# 20190906TPS40200CV.net
KiCad netlist of a schematic drawn in Altium Designer
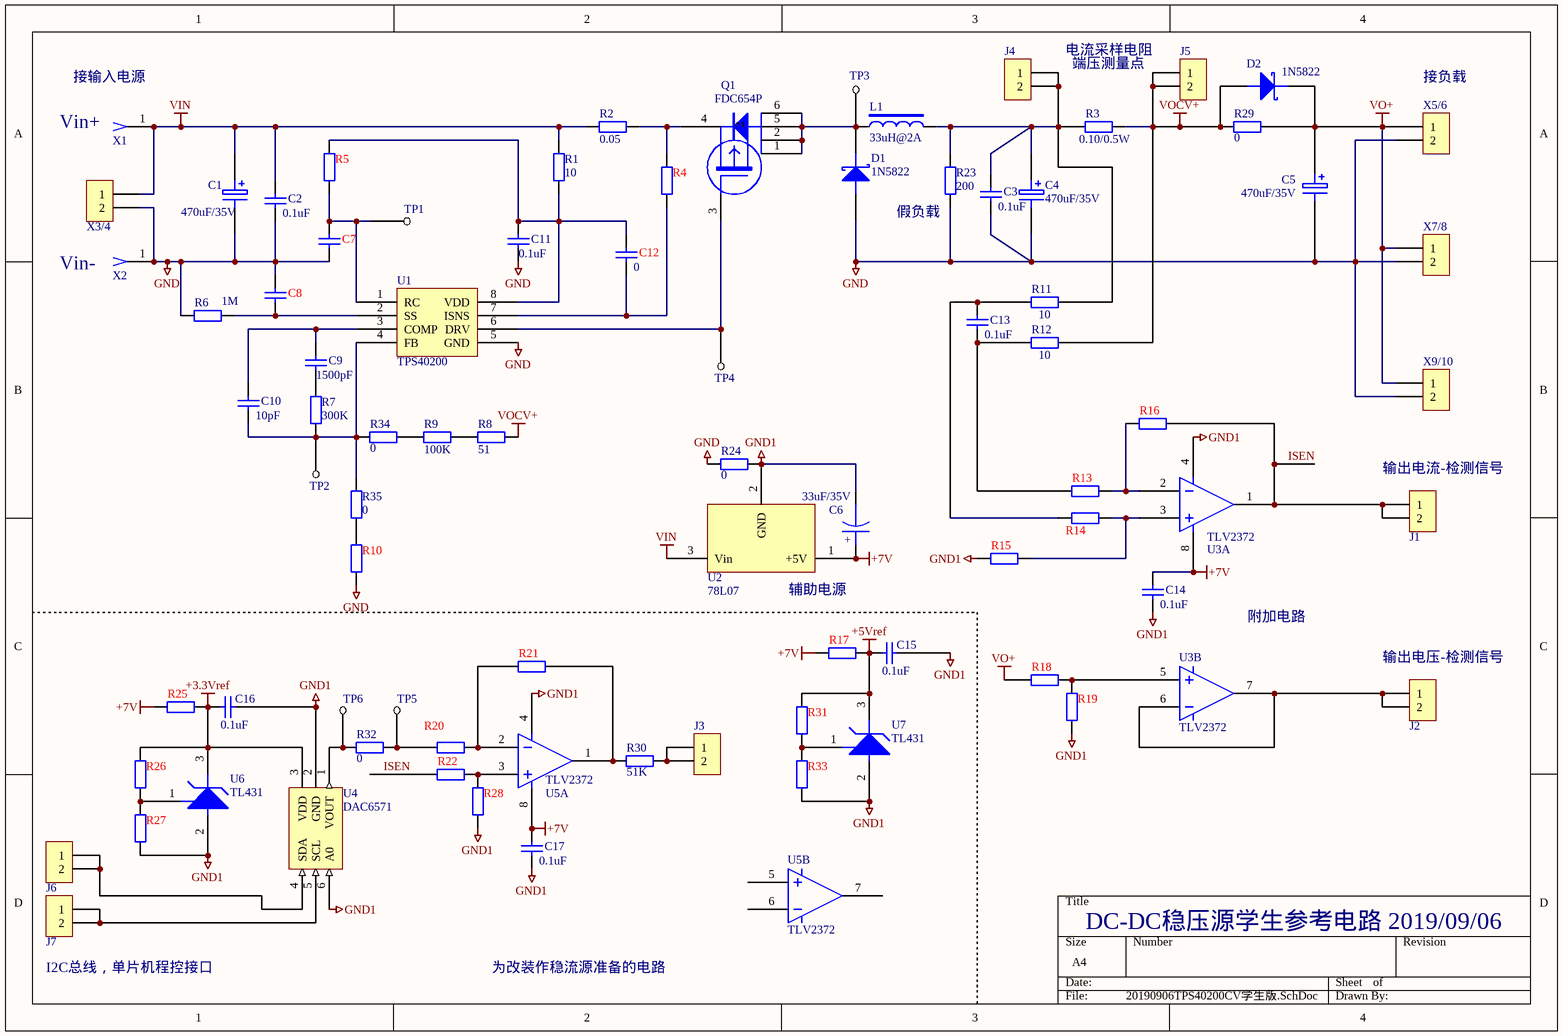
[diagram p0: 20190906TPS40200CV学生版.SchDoc]

(export (version "E")
  (design (tool "Eeschema 10.0.6"))
  (components
    (comp (ref "C1")
      (value "470uF/35V")
      (footprint "RB5-10.5")
      (description "Electrolytic Capacitor")
      (libsource (lib "*") (part "ELECTRO1"))
    )
    (comp (ref "C2")
      (value "0.1uF")
      (footprint "0805-1")
      (description "Capacitor")
      (fields (field (name "PUBLISHER") "Altium Limited"))
      (libsource (lib "Miscellaneous Devices") (part "Cap"))
    )
    (comp (ref "C3")
      (value "0.1uF")
      (footprint "0805-1")
      (description "Capacitor")
      (fields (field (name "PUBLISHER") "Altium Limited"))
      (libsource (lib "Miscellaneous Devices") (part "Cap"))
    )
    (comp (ref "C4")
      (value "470uF/35V")
      (footprint "RB5-10.5")
      (description "Electrolytic Capacitor")
      (libsource (lib "*") (part "ELECTRO1"))
    )
    (comp (ref "C5")
      (value "470uF/35V")
      (footprint "RB5-10.5")
      (description "Electrolytic Capacitor")
      (libsource (lib "*") (part "ELECTRO1"))
    )
    (comp (ref "C6")
      (value "33uF/35V")
      (footprint "C-RB-8")
      (description "Capacitor")
      (libsource (lib "*") (part "CAPACITOR POL"))
    )
    (comp (ref "C7")
      (value "~")
      (footprint "0805-1")
      (description "Capacitor")
      (fields (field (name "PUBLISHER") "Altium Limited"))
      (libsource (lib "Miscellaneous Devices") (part "Cap"))
    )
    (comp (ref "C8")
      (value "~")
      (footprint "0805-1")
      (description "Capacitor")
      (fields (field (name "PUBLISHER") "Altium Limited"))
      (libsource (lib "Miscellaneous Devices") (part "Cap"))
    )
    (comp (ref "C9")
      (value "1500pF")
      (footprint "0805-1")
      (description "Capacitor")
      (fields (field (name "PUBLISHER") "Altium Limited"))
      (libsource (lib "Miscellaneous Devices") (part "Cap"))
    )
    (comp (ref "C10")
      (value "10pF")
      (footprint "0805-1")
      (description "Capacitor")
      (fields (field (name "PUBLISHER") "Altium Limited"))
      (libsource (lib "Miscellaneous Devices") (part "Cap"))
    )
    (comp (ref "C11")
      (value "0.1uF")
      (footprint "0805-1")
      (description "Capacitor")
      (fields (field (name "PUBLISHER") "Altium Limited"))
      (libsource (lib "Miscellaneous Devices") (part "Cap"))
    )
    (comp (ref "C12")
      (value "0")
      (footprint "0805-1")
      (description "Capacitor")
      (fields (field (name "PUBLISHER") "Altium Limited"))
      (libsource (lib "Miscellaneous Devices") (part "Cap"))
    )
    (comp (ref "C13")
      (value "0.1uF")
      (footprint "0805-1")
      (description "Capacitor")
      (fields (field (name "PUBLISHER") "Altium Limited"))
      (libsource (lib "Miscellaneous Devices") (part "Cap"))
    )
    (comp (ref "C14")
      (value "0.1uF")
      (footprint "0805-1")
      (description "Capacitor")
      (fields (field (name "PUBLISHER") "Altium Limited"))
      (libsource (lib "Miscellaneous Devices") (part "Cap"))
    )
    (comp (ref "C15")
      (value "0.1uF")
      (footprint "CC2012-0805")
      (description "Capacitor")
      (fields (field (name "PUBLISHER") "Altium Limited"))
      (libsource (lib "Miscellaneous Devices") (part "Cap"))
    )
    (comp (ref "C16")
      (value "0.1uF")
      (footprint "0805-1")
      (description "Capacitor")
      (fields (field (name "PUBLISHER") "Altium Limited"))
      (libsource (lib "Miscellaneous Devices") (part "Cap"))
    )
    (comp (ref "C17")
      (value "0.1uF")
      (footprint "0805-1")
      (description "Capacitor")
      (fields (field (name "PUBLISHER") "Altium Limited"))
      (libsource (lib "Miscellaneous Devices") (part "Cap"))
    )
    (comp (ref "D1")
      (value "1N5822")
      (footprint "DIODE-0.7")
      (description "Schottky Diode")
      (libsource (lib "*") (part "DIODE SCHOTTKY"))
    )
    (comp (ref "D2")
      (value "1N5822")
      (footprint "DIODE-0.7")
      (description "Schottky Diode")
      (libsource (lib "*") (part "DIODE SCHOTTKY"))
    )
    (comp (ref "J1")
      (value "SIP2")
      (footprint "HDR1X2")
      (description "Connector")
      (libsource (lib "*") (part "CON2"))
    )
    (comp (ref "J2")
      (value "SIP2")
      (footprint "HDR1X2")
      (description "Connector")
      (libsource (lib "*") (part "CON2"))
    )
    (comp (ref "J3")
      (value "SIP2")
      (footprint "HDR1X2")
      (description "Connector")
      (libsource (lib "*") (part "CON2"))
    )
    (comp (ref "J4")
      (value "SIP2")
      (footprint "HDR1X2")
      (description "Connector")
      (libsource (lib "") (part "CON2_1"))
    )
    (comp (ref "J5")
      (value "SIP2")
      (footprint "HDR1X2")
      (description "Connector")
      (libsource (lib "*") (part "CON2"))
    )
    (comp (ref "J6")
      (value "SIP2")
      (footprint "HDR1X2")
      (description "Connector")
      (libsource (lib "") (part "CON2_1"))
    )
    (comp (ref "J7")
      (value "SIP2")
      (footprint "HDR1X2")
      (description "Connector")
      (libsource (lib "") (part "CON2_1"))
    )
    (comp (ref "L1")
      (value "33uH@2A")
      (footprint "L2")
      (description "Inductor")
      (libsource (lib "*") (part "INDUCTOR2"))
    )
    (comp (ref "Q1")
      (value "FDC654P")
      (footprint "SOT23-6")
      (description "Mosfet")
      (libsource (lib "origin_Project1") (part "FDC654P"))
    )
    (comp (ref "R1")
      (value "10")
      (footprint "0805-1")
      (description "Resistor")
      (fields (field (name "PUBLISHER") "Altium Limited"))
      (libsource (lib "") (part "Res2_2"))
    )
    (comp (ref "R2")
      (value "0.05")
      (footprint "2512")
      (description "Resistor")
      (fields (field (name "PUBLISHER") "Altium Limited"))
      (libsource (lib "Miscellaneous Devices") (part "Res2"))
    )
    (comp (ref "R3")
      (value "0.10/0.5W")
      (footprint "2512")
      (description "Resistor")
      (fields (field (name "PUBLISHER") "Altium Limited"))
      (libsource (lib "Miscellaneous Devices") (part "Res2"))
    )
    (comp (ref "R4")
      (value "~")
      (footprint "0805-1")
      (description "Resistor")
      (fields (field (name "PUBLISHER") "Altium Limited"))
      (libsource (lib "") (part "Res2_2"))
    )
    (comp (ref "R5")
      (value "~")
      (footprint "0805-1")
      (description "Resistor")
      (fields (field (name "PUBLISHER") "Altium Limited"))
      (libsource (lib "") (part "Res2_2"))
    )
    (comp (ref "R6")
      (value "1M")
      (footprint "0805-1")
      (description "Resistor")
      (fields (field (name "PUBLISHER") "Altium Limited"))
      (libsource (lib "Miscellaneous Devices") (part "Res2"))
    )
    (comp (ref "R7")
      (value "300K")
      (footprint "0805-1")
      (description "Resistor")
      (fields (field (name "PUBLISHER") "Altium Limited"))
      (libsource (lib "") (part "Res2_2"))
    )
    (comp (ref "R8")
      (value "51")
      (footprint "0805-1")
      (description "Resistor")
      (fields (field (name "PUBLISHER") "Altium Limited"))
      (libsource (lib "Miscellaneous Devices") (part "Res2"))
    )
    (comp (ref "R9")
      (value "100K")
      (footprint "0805-1")
      (description "Resistor")
      (fields (field (name "PUBLISHER") "Altium Limited"))
      (libsource (lib "Miscellaneous Devices") (part "Res2"))
    )
    (comp (ref "R10")
      (value "~")
      (footprint "0805-1")
      (description "Resistor")
      (fields (field (name "PUBLISHER") "Altium Limited"))
      (libsource (lib "") (part "Res2_2"))
    )
    (comp (ref "R11")
      (value "10")
      (footprint "0805-1")
      (description "Resistor")
      (fields (field (name "PUBLISHER") "Altium Limited"))
      (libsource (lib "Miscellaneous Devices") (part "Res2"))
    )
    (comp (ref "R12")
      (value "10")
      (footprint "0805-1")
      (description "Resistor")
      (fields (field (name "PUBLISHER") "Altium Limited"))
      (libsource (lib "Miscellaneous Devices") (part "Res2"))
    )
    (comp (ref "R13")
      (value "~")
      (footprint "0805-1")
      (description "Resistor")
      (fields (field (name "PUBLISHER") "Altium Limited"))
      (libsource (lib "Miscellaneous Devices") (part "Res2"))
    )
    (comp (ref "R14")
      (value "~")
      (footprint "0805-1")
      (description "Resistor")
      (fields (field (name "PUBLISHER") "Altium Limited"))
      (libsource (lib "Miscellaneous Devices") (part "Res2"))
    )
    (comp (ref "R15")
      (value "~")
      (footprint "0805-1")
      (description "Resistor")
      (fields (field (name "PUBLISHER") "Altium Limited"))
      (libsource (lib "Miscellaneous Devices") (part "Res2"))
    )
    (comp (ref "R16")
      (value "~")
      (footprint "0805-1")
      (description "Resistor")
      (fields (field (name "PUBLISHER") "Altium Limited"))
      (libsource (lib "Miscellaneous Devices") (part "Res2"))
    )
    (comp (ref "R17")
      (value "~")
      (footprint "CC2012-0805")
      (description "Resistor")
      (fields (field (name "PUBLISHER") "Altium Limited"))
      (libsource (lib "") (part "Res2_1"))
    )
    (comp (ref "R18")
      (value "~")
      (footprint "0805-1")
      (description "Resistor")
      (fields (field (name "PUBLISHER") "Altium Limited"))
      (libsource (lib "Miscellaneous Devices") (part "Res2"))
    )
    (comp (ref "R19")
      (value "~")
      (footprint "0805-1")
      (description "Resistor")
      (fields (field (name "PUBLISHER") "Altium Limited"))
      (libsource (lib "") (part "Res2_2"))
    )
    (comp (ref "R20")
      (value "~")
      (footprint "0805-1")
      (description "Resistor")
      (fields (field (name "PUBLISHER") "Altium Limited"))
      (libsource (lib "Miscellaneous Devices") (part "Res2"))
    )
    (comp (ref "R21")
      (value "~")
      (footprint "0805-1")
      (description "Resistor")
      (fields (field (name "PUBLISHER") "Altium Limited"))
      (libsource (lib "Miscellaneous Devices") (part "Res2"))
    )
    (comp (ref "R22")
      (value "~")
      (footprint "0805-1")
      (description "Resistor")
      (fields (field (name "PUBLISHER") "Altium Limited"))
      (libsource (lib "Miscellaneous Devices") (part "Res2"))
    )
    (comp (ref "R23")
      (value "200")
      (footprint "0805-1")
      (description "Resistor")
      (fields (field (name "PUBLISHER") "Altium Limited"))
      (libsource (lib "") (part "Res2_2"))
    )
    (comp (ref "R24")
      (value "0")
      (footprint "0805-1")
      (description "Resistor")
      (fields (field (name "PUBLISHER") "Altium Limited"))
      (libsource (lib "") (part "Res2_1"))
    )
    (comp (ref "R25")
      (value "~")
      (footprint "0805-1")
      (description "Resistor")
      (fields (field (name "PUBLISHER") "Altium Limited"))
      (libsource (lib "") (part "Res2_1"))
    )
    (comp (ref "R26")
      (value "~")
      (footprint "0805-1")
      (description "Resistor")
      (fields (field (name "PUBLISHER") "Altium Limited"))
      (libsource (lib "") (part "Res2_3"))
    )
    (comp (ref "R27")
      (value "~")
      (footprint "0805-1")
      (description "Resistor")
      (fields (field (name "PUBLISHER") "Altium Limited"))
      (libsource (lib "") (part "Res2_3"))
    )
    (comp (ref "R28")
      (value "~")
      (footprint "0805-1")
      (description "Resistor")
      (fields (field (name "PUBLISHER") "Altium Limited"))
      (libsource (lib "") (part "Res2_2"))
    )
    (comp (ref "R29")
      (value "0")
      (footprint "0805-1")
      (description "Resistor")
      (fields (field (name "PUBLISHER") "Altium Limited"))
      (libsource (lib "") (part "Res2_1"))
    )
    (comp (ref "R30")
      (value "51K")
      (footprint "0805-1")
      (description "Resistor")
      (fields (field (name "PUBLISHER") "Altium Limited"))
      (libsource (lib "Miscellaneous Devices") (part "Res2"))
    )
    (comp (ref "R31")
      (value "~")
      (footprint "CC2012-0805")
      (description "Resistor")
      (fields (field (name "PUBLISHER") "Altium Limited"))
      (libsource (lib "") (part "Res2_3"))
    )
    (comp (ref "R32")
      (value "0")
      (footprint "CC2012-0805")
      (description "Resistor")
      (fields (field (name "PUBLISHER") "Altium Limited"))
      (libsource (lib "") (part "Res2_1"))
    )
    (comp (ref "R33")
      (value "~")
      (footprint "CC2012-0805")
      (description "Resistor")
      (fields (field (name "PUBLISHER") "Altium Limited"))
      (libsource (lib "") (part "Res2_3"))
    )
    (comp (ref "R34")
      (value "0")
      (footprint "CC2012-0805")
      (description "Resistor")
      (fields (field (name "PUBLISHER") "Altium Limited"))
      (libsource (lib "") (part "Res2_1"))
    )
    (comp (ref "R35")
      (value "0")
      (footprint "CC2012-0805")
      (description "Resistor")
      (fields (field (name "PUBLISHER") "Altium Limited"))
      (libsource (lib "") (part "Res2_2"))
    )
    (comp (ref "TP1") (value "NULL") (footprint "PIN1") (libsource (lib "YY_sch0302") (part "TEST")))
    (comp (ref "TP2") (value "NULL") (footprint "PIN1") (libsource (lib "YY_sch0302") (part "TEST")))
    (comp (ref "TP3") (value "NULL") (footprint "PIN1") (libsource (lib "YY_sch0302") (part "TEST")))
    (comp (ref "TP4") (value "NULL") (footprint "PIN1") (libsource (lib "YY_sch0302") (part "TEST")))
    (comp (ref "TP5") (value "NULL") (footprint "PIN1") (libsource (lib "YY_sch0302") (part "TEST")))
    (comp (ref "TP6") (value "NULL") (footprint "PIN1") (libsource (lib "YY_sch0302") (part "TEST")))
    (comp (ref "U1")
      (value "TPS40200")
      (footprint "SOIC8_N")
      (description "Chip")
      (libsource (lib "*") (part "TPS40200"))
    )
    (comp (ref "U2")
      (value "78L07")
      (footprint "TO-92A")
      (description "Chip")
      (libsource (lib "*") (part "MC7805T"))
    )
    (comp (ref "U3")
      (value "TLV2372")
      (footprint "DIP8")
      (description "Chip")
      (libsource (lib "*") (part "1458"))
    )
    (comp (ref "U4")
      (value "DAC6571")
      (footprint "SOT23-6")
      (description "Chip")
      (libsource (lib "YY_sch0302") (part "DAC6571"))
    )
    (comp (ref "U5")
      (value "TLV2372")
      (footprint "DIP8")
      (description "Chip")
      (libsource (lib "*") (part "1458"))
    )
    (comp (ref "U6")
      (value "TL431")
      (footprint "TO-92A")
      (description "Chip")
      (libsource (lib "YY_sch0302") (part "TL431"))
    )
    (comp (ref "U7")
      (value "TL431")
      (footprint "TO-92A")
      (description "Chip")
      (libsource (lib "YY_sch0302") (part "TL431"))
    )
    (comp (ref "X1")
      (value "BANANA")
      (footprint "HOLE 6-13")
      (description "Connector")
      (libsource (lib "*") (part "INPUT"))
    )
    (comp (ref "X2")
      (value "BANANA")
      (footprint "HOLE 6-13")
      (description "Connector")
      (libsource (lib "*") (part "INPUT"))
    )
    (comp (ref "X3/4")
      (value "PIN2-160mil")
      (footprint "SH30")
      (description "Connector")
      (libsource (lib "") (part "CON2_1"))
    )
    (comp (ref "X5/6")
      (value "PIN2-160mil")
      (footprint "SH30")
      (description "Connector")
      (libsource (lib "*") (part "CON2"))
    )
    (comp (ref "X7/8")
      (value "PIN2-160mil")
      (footprint "SH30")
      (description "Connector")
      (libsource (lib "*") (part "CON2"))
    )
    (comp (ref "X9/10")
      (value "PIN2-160mil")
      (footprint "SH30")
      (description "Connector")
      (libsource (lib "*") (part "CON2"))
    )
  )
  (nets
    (net (code "1") (name "+3.3Vref") (class "Default")
      (node (ref "C16") (pin "1") (pinfunction "1_1") (pintype "passive"))
      (node (ref "R25") (pin "2") (pinfunction "2_2") (pintype "passive"))
      (node (ref "R26") (pin "1") (pinfunction "1_1") (pintype "passive"))
      (node (ref "U4") (pin "3") (pinfunction "VDD_3") (pintype "power_in"))
      (node (ref "U6") (pin "3") (pinfunction "K_3") (pintype "passive"))
    )
    (net (code "2") (name "+5Vref") (class "Default")
      (node (ref "C15") (pin "1") (pinfunction "1_1") (pintype "passive"))
      (node (ref "R17") (pin "2") (pinfunction "2_2") (pintype "passive"))
      (node (ref "R31") (pin "1") (pinfunction "1_1") (pintype "passive"))
      (node (ref "U7") (pin "3") (pinfunction "K_3") (pintype "passive"))
    )
    (net (code "3") (name "+7V") (class "Default")
      (node (ref "C14") (pin "1") (pinfunction "1_1") (pintype "passive"))
      (node (ref "C17") (pin "1") (pinfunction "1_1") (pintype "passive"))
      (node (ref "C6") (pin "1") (pinfunction "1_1") (pintype "passive"))
      (node (ref "R17") (pin "1") (pinfunction "1_1") (pintype "passive"))
      (node (ref "R25") (pin "1") (pinfunction "1_1") (pintype "passive"))
      (node (ref "U2") (pin "1") (pinfunction "+5V_1") (pintype "passive"))
      (node (ref "U3") (pin "8") (pintype "passive"))
      (node (ref "U5") (pin "8") (pintype "passive"))
    )
    (net (code "4") (name "/ISEN") (class "Default")
      (node (ref "J1") (pin "1") (pinfunction "1_1") (pintype "passive"))
      (node (ref "J1") (pin "2") (pinfunction "2_2") (pintype "passive"))
      (node (ref "R16") (pin "1") (pinfunction "1_1") (pintype "passive"))
      (node (ref "R22") (pin "2") (pinfunction "2_2") (pintype "passive"))
      (node (ref "U3") (pin "1") (pintype "passive"))
    )
    (net (code "5") (name "GND") (class "Default")
      (node (ref "C1") (pin "2") (pinfunction "2_2") (pintype "passive"))
      (node (ref "C11") (pin "2") (pinfunction "2_2") (pintype "passive"))
      (node (ref "C2") (pin "2") (pinfunction "2_2") (pintype "passive"))
      (node (ref "C3") (pin "2") (pinfunction "2_2") (pintype "passive"))
      (node (ref "C4") (pin "2") (pinfunction "2_2") (pintype "passive"))
      (node (ref "C5") (pin "2") (pinfunction "2_2") (pintype "passive"))
      (node (ref "C7") (pin "2") (pinfunction "2_2") (pintype "passive"))
      (node (ref "C8") (pin "1") (pinfunction "1_1") (pintype "passive"))
      (node (ref "D1") (pin "1") (pinfunction "1_1") (pintype "passive"))
      (node (ref "R10") (pin "1") (pinfunction "1_1") (pintype "passive"))
      (node (ref "R23") (pin "1") (pinfunction "1_1") (pintype "passive"))
      (node (ref "R24") (pin "1") (pinfunction "1_1") (pintype "passive"))
      (node (ref "R6") (pin "2") (pinfunction "2_2") (pintype "passive"))
      (node (ref "U1") (pin "5") (pinfunction "GND_5") (pintype "passive"))
      (node (ref "X2") (pin "1") (pintype "passive"))
      (node (ref "X3/4") (pin "2") (pinfunction "2_2") (pintype "passive"))
      (node (ref "X5/6") (pin "2") (pinfunction "2_2") (pintype "passive"))
      (node (ref "X7/8") (pin "2") (pinfunction "2_2") (pintype "passive"))
      (node (ref "X9/10") (pin "2") (pinfunction "2_2") (pintype "passive"))
    )
    (net (code "6") (name "GND1") (class "Default")
      (node (ref "C14") (pin "2") (pinfunction "2_2") (pintype "passive"))
      (node (ref "C15") (pin "2") (pinfunction "2_2") (pintype "passive"))
      (node (ref "C16") (pin "2") (pinfunction "2_2") (pintype "passive"))
      (node (ref "C17") (pin "2") (pinfunction "2_2") (pintype "passive"))
      (node (ref "C6") (pin "2") (pinfunction "2_2") (pintype "passive"))
      (node (ref "R15") (pin "2") (pinfunction "2_2") (pintype "passive"))
      (node (ref "R19") (pin "1") (pinfunction "1_1") (pintype "passive"))
      (node (ref "R24") (pin "2") (pinfunction "2_2") (pintype "passive"))
      (node (ref "R27") (pin "2") (pinfunction "2_2") (pintype "passive"))
      (node (ref "R28") (pin "1") (pinfunction "1_1") (pintype "passive"))
      (node (ref "R33") (pin "2") (pinfunction "2_2") (pintype "passive"))
      (node (ref "U2") (pin "2") (pinfunction "GND_2") (pintype "passive"))
      (node (ref "U3") (pin "4") (pintype "passive"))
      (node (ref "U4") (pin "2") (pinfunction "GND_2") (pintype "power_in"))
      (node (ref "U4") (pin "6") (pinfunction "A0_6") (pintype "input"))
      (node (ref "U5") (pin "4") (pintype "passive"))
      (node (ref "U6") (pin "2") (pinfunction "A_2") (pintype "passive"))
      (node (ref "U7") (pin "2") (pinfunction "A_2") (pintype "passive"))
    )
    (net (code "7") (name "Net-(C3-Pad1)") (class "Default")
      (node (ref "C3") (pin "1") (pinfunction "1_1") (pintype "passive"))
      (node (ref "C4") (pin "1") (pinfunction "1_1") (pintype "passive"))
      (node (ref "J4") (pin "1") (pinfunction "1_1") (pintype "passive"))
      (node (ref "J4") (pin "2") (pinfunction "2_2") (pintype "passive"))
      (node (ref "L1") (pin "10") (pintype "passive"))
      (node (ref "R11") (pin "1") (pinfunction "1_1") (pintype "passive"))
      (node (ref "R23") (pin "2") (pinfunction "2_2") (pintype "passive"))
      (node (ref "R3") (pin "2") (pinfunction "2_2") (pintype "passive"))
    )
    (net (code "8") (name "Net-(C9-Pad2)") (class "Default")
      (node (ref "C9") (pin "2") (pinfunction "2_2") (pintype "passive"))
      (node (ref "R7") (pin "2") (pinfunction "2_2") (pintype "passive"))
    )
    (net (code "9") (name "Net-(C13-Pad1)") (class "Default")
      (node (ref "C13") (pin "1") (pinfunction "1_1") (pintype "passive"))
      (node (ref "R12") (pin "2") (pinfunction "2_2") (pintype "passive"))
      (node (ref "R13") (pin "2") (pinfunction "2_2") (pintype "passive"))
    )
    (net (code "10") (name "Net-(C13-Pad2)") (class "Default")
      (node (ref "C13") (pin "2") (pinfunction "2_2") (pintype "passive"))
      (node (ref "R11") (pin "2") (pinfunction "2_2") (pintype "passive"))
      (node (ref "R14") (pin "2") (pinfunction "2_2") (pintype "passive"))
    )
    (net (code "11") (name "Net-(D1-Pad2)") (class "Default")
      (node (ref "D1") (pin "2") (pinfunction "2_2") (pintype "passive"))
      (node (ref "L1") (pin "1") (pintype "passive"))
      (node (ref "Q1") (pin "1") (pinfunction "D_1") (pintype "passive"))
      (node (ref "Q1") (pin "2") (pinfunction "D_2") (pintype "passive"))
      (node (ref "Q1") (pin "5") (pinfunction "D_5") (pintype "passive"))
      (node (ref "Q1") (pin "6") (pinfunction "D_6") (pintype "passive"))
      (node (ref "TP3") (pin "1") (pinfunction "1_1") (pintype "passive"))
    )
    (net (code "12") (name "Net-(J2-Pad1)") (class "Default")
      (node (ref "J2") (pin "1") (pinfunction "1_1") (pintype "passive"))
      (node (ref "J2") (pin "2") (pinfunction "2_2") (pintype "passive"))
      (node (ref "U3") (pin "6") (pintype "passive"))
      (node (ref "U3") (pin "7") (pintype "passive"))
    )
    (net (code "13") (name "Net-(J3-Pad1)") (class "Default")
      (node (ref "J3") (pin "1") (pinfunction "1_1") (pintype "passive"))
      (node (ref "J3") (pin "2") (pinfunction "2_2") (pintype "passive"))
      (node (ref "R30") (pin "1") (pinfunction "1_1") (pintype "passive"))
    )
    (net (code "14") (name "Net-(Q1-G)") (class "Default")
      (node (ref "Q1") (pin "3") (pinfunction "G_3") (pintype "passive"))
      (node (ref "TP4") (pin "1") (pinfunction "1_1") (pintype "passive"))
      (node (ref "U1") (pin "6") (pinfunction "DRV_6") (pintype "passive"))
    )
    (net (code "15") (name "Net-(Q1-S)") (class "Default")
      (node (ref "Q1") (pin "4") (pinfunction "S_4") (pintype "passive"))
      (node (ref "R2") (pin "1") (pinfunction "1_1") (pintype "passive"))
      (node (ref "R4") (pin "2") (pinfunction "2_2") (pintype "passive"))
    )
    (net (code "16") (name "Net-(R8-Pad2)") (class "Default")
      (node (ref "R8") (pin "2") (pinfunction "2_2") (pintype "passive"))
      (node (ref "R9") (pin "1") (pinfunction "1_1") (pintype "passive"))
    )
    (net (code "17") (name "Net-(R10-Pad2)") (class "Default")
      (node (ref "R10") (pin "2") (pinfunction "2_2") (pintype "passive"))
      (node (ref "R35") (pin "1") (pinfunction "1_1") (pintype "passive"))
    )
    (net (code "18") (name "Net-(R13-Pad1)") (class "Default")
      (node (ref "R13") (pin "1") (pinfunction "1_1") (pintype "passive"))
      (node (ref "R16") (pin "2") (pinfunction "2_2") (pintype "passive"))
      (node (ref "U3") (pin "2") (pintype "passive"))
    )
    (net (code "19") (name "Net-(R14-Pad1)") (class "Default")
      (node (ref "R14") (pin "1") (pinfunction "1_1") (pintype "passive"))
      (node (ref "R15") (pin "1") (pinfunction "1_1") (pintype "passive"))
      (node (ref "U3") (pin "3") (pintype "passive"))
    )
    (net (code "20") (name "Net-(R18-Pad1)") (class "Default")
      (node (ref "R18") (pin "1") (pinfunction "1_1") (pintype "passive"))
      (node (ref "R19") (pin "2") (pinfunction "2_2") (pintype "passive"))
      (node (ref "U3") (pin "5") (pintype "passive"))
    )
    (net (code "21") (name "Net-(R20-Pad1)") (class "Default")
      (node (ref "R20") (pin "1") (pinfunction "1_1") (pintype "passive"))
      (node (ref "R21") (pin "2") (pinfunction "2_2") (pintype "passive"))
      (node (ref "U5") (pin "2") (pintype "passive"))
    )
    (net (code "22") (name "Net-(R20-Pad2)") (class "Default")
      (node (ref "R20") (pin "2") (pinfunction "2_2") (pintype "passive"))
      (node (ref "R32") (pin "2") (pinfunction "2_2") (pintype "passive"))
      (node (ref "TP5") (pin "1") (pinfunction "1_1") (pintype "passive"))
    )
    (net (code "23") (name "Net-(R21-Pad1)") (class "Default")
      (node (ref "R21") (pin "1") (pinfunction "1_1") (pintype "passive"))
      (node (ref "R30") (pin "2") (pinfunction "2_2") (pintype "passive"))
      (node (ref "U5") (pin "1") (pintype "passive"))
    )
    (net (code "24") (name "Net-(R22-Pad1)") (class "Default")
      (node (ref "R22") (pin "1") (pinfunction "1_1") (pintype "passive"))
      (node (ref "R28") (pin "2") (pinfunction "2_2") (pintype "passive"))
      (node (ref "U5") (pin "3") (pintype "passive"))
    )
    (net (code "25") (name "Net-(R34-Pad2)") (class "Default")
      (node (ref "R34") (pin "2") (pinfunction "2_2") (pintype "passive"))
      (node (ref "R9") (pin "2") (pinfunction "2_2") (pintype "passive"))
    )
    (net (code "26") (name "Net-(U1-COMP)") (class "Default")
      (node (ref "C10") (pin "1") (pinfunction "1_1") (pintype "passive"))
      (node (ref "C9") (pin "1") (pinfunction "1_1") (pintype "passive"))
      (node (ref "U1") (pin "3") (pinfunction "COMP_3") (pintype "passive"))
    )
    (net (code "27") (name "Net-(U1-FB)") (class "Default")
      (node (ref "C10") (pin "2") (pinfunction "2_2") (pintype "passive"))
      (node (ref "R34") (pin "1") (pinfunction "1_1") (pintype "passive"))
      (node (ref "R35") (pin "2") (pinfunction "2_2") (pintype "passive"))
      (node (ref "R7") (pin "1") (pinfunction "1_1") (pintype "passive"))
      (node (ref "TP2") (pin "1") (pinfunction "1_1") (pintype "passive"))
      (node (ref "U1") (pin "4") (pinfunction "FB_4") (pintype "passive"))
    )
    (net (code "28") (name "Net-(U1-ISNS)") (class "Default")
      (node (ref "C12") (pin "2") (pinfunction "2_2") (pintype "passive"))
      (node (ref "R4") (pin "1") (pinfunction "1_1") (pintype "passive"))
      (node (ref "U1") (pin "7") (pinfunction "ISNS_7") (pintype "passive"))
    )
    (net (code "29") (name "Net-(U1-RC)") (class "Default")
      (node (ref "C7") (pin "1") (pinfunction "1_1") (pintype "passive"))
      (node (ref "R5") (pin "1") (pinfunction "1_1") (pintype "passive"))
      (node (ref "TP1") (pin "1") (pinfunction "1_1") (pintype "passive"))
      (node (ref "U1") (pin "1") (pinfunction "RC_1") (pintype "passive"))
    )
    (net (code "30") (name "Net-(U1-SS)") (class "Default")
      (node (ref "C8") (pin "2") (pinfunction "2_2") (pintype "passive"))
      (node (ref "R6") (pin "1") (pinfunction "1_1") (pintype "passive"))
      (node (ref "U1") (pin "2") (pinfunction "SS_2") (pintype "passive"))
    )
    (net (code "31") (name "Net-(U1-VDD)") (class "Default")
      (node (ref "C11") (pin "1") (pinfunction "1_1") (pintype "passive"))
      (node (ref "C12") (pin "1") (pinfunction "1_1") (pintype "passive"))
      (node (ref "R1") (pin "1") (pinfunction "1_1") (pintype "passive"))
      (node (ref "R5") (pin "2") (pinfunction "2_2") (pintype "passive"))
      (node (ref "U1") (pin "8") (pinfunction "VDD_8") (pintype "passive"))
    )
    (net (code "32") (name "Net-(U4-SCL)") (class "Default")
      (node (ref "J7") (pin "1") (pinfunction "1_1") (pintype "passive"))
      (node (ref "J7") (pin "2") (pinfunction "2_2") (pintype "passive"))
      (node (ref "U4") (pin "5") (pinfunction "SCL_5") (pintype "input"))
    )
    (net (code "33") (name "Net-(U4-SDA)") (class "Default")
      (node (ref "J6") (pin "1") (pinfunction "1_1") (pintype "passive"))
      (node (ref "J6") (pin "2") (pinfunction "2_2") (pintype "passive"))
      (node (ref "U4") (pin "4") (pinfunction "SDA_4") (pintype "input"))
    )
    (net (code "34") (name "Net-(U4-VOUT)") (class "Default")
      (node (ref "R32") (pin "1") (pinfunction "1_1") (pintype "passive"))
      (node (ref "TP6") (pin "1") (pinfunction "1_1") (pintype "passive"))
      (node (ref "U4") (pin "1") (pinfunction "VOUT_1") (pintype "output"))
    )
    (net (code "35") (name "Net-(U6-R)") (class "Default")
      (node (ref "R26") (pin "2") (pinfunction "2_2") (pintype "passive"))
      (node (ref "R27") (pin "1") (pinfunction "1_1") (pintype "passive"))
      (node (ref "U6") (pin "1") (pinfunction "R_1") (pintype "passive"))
    )
    (net (code "36") (name "Net-(U7-R)") (class "Default")
      (node (ref "R31") (pin "2") (pinfunction "2_2") (pintype "passive"))
      (node (ref "R33") (pin "1") (pinfunction "1_1") (pintype "passive"))
      (node (ref "U7") (pin "1") (pinfunction "R_1") (pintype "passive"))
    )
    (net (code "37") (name "VIN") (class "Default")
      (node (ref "C1") (pin "1") (pinfunction "1_1") (pintype "passive"))
      (node (ref "C2") (pin "1") (pinfunction "1_1") (pintype "passive"))
      (node (ref "R1") (pin "2") (pinfunction "2_2") (pintype "passive"))
      (node (ref "R2") (pin "2") (pinfunction "2_2") (pintype "passive"))
      (node (ref "U2") (pin "3") (pinfunction "Vin_3") (pintype "passive"))
      (node (ref "X1") (pin "1") (pintype "passive"))
      (node (ref "X3/4") (pin "1") (pinfunction "1_1") (pintype "passive"))
    )
    (net (code "38") (name "VO+") (class "Default")
      (node (ref "C5") (pin "1") (pinfunction "1_1") (pintype "passive"))
      (node (ref "D2") (pin "2") (pinfunction "2_2") (pintype "passive"))
      (node (ref "R18") (pin "2") (pinfunction "2_2") (pintype "passive"))
      (node (ref "R29") (pin "2") (pinfunction "2_2") (pintype "passive"))
      (node (ref "X5/6") (pin "1") (pinfunction "1_1") (pintype "passive"))
      (node (ref "X7/8") (pin "1") (pinfunction "1_1") (pintype "passive"))
      (node (ref "X9/10") (pin "1") (pinfunction "1_1") (pintype "passive"))
    )
    (net (code "39") (name "VOCV+") (class "Default")
      (node (ref "D2") (pin "1") (pinfunction "1_1") (pintype "passive"))
      (node (ref "J5") (pin "1") (pinfunction "1_1") (pintype "passive"))
      (node (ref "J5") (pin "2") (pinfunction "2_2") (pintype "passive"))
      (node (ref "R12") (pin "1") (pinfunction "1_1") (pintype "passive"))
      (node (ref "R29") (pin "1") (pinfunction "1_1") (pintype "passive"))
      (node (ref "R3") (pin "1") (pinfunction "1_1") (pintype "passive"))
      (node (ref "R8") (pin "1") (pinfunction "1_1") (pintype "passive"))
    )
    (net (code "40") (name "unconnected-(Q1-D-Pad2)") (class "Default")
      (node (ref "Q1") (pin "2") (pinfunction "D_2") (pintype "passive"))
    )
    (net (code "41") (name "unconnected-(U5-Pad5)") (class "Default")
      (node (ref "U5") (pin "5") (pintype "passive"))
    )
    (net (code "42") (name "unconnected-(U5-Pad6)") (class "Default")
      (node (ref "U5") (pin "6") (pintype "passive"))
    )
    (net (code "43") (name "unconnected-(U5-Pad7)") (class "Default")
      (node (ref "U5") (pin "7") (pintype "passive"))
    )
  )
)
